# gnss_quectel_lc29hea.net
KiCad netlist of a schematic drawn in Altium Designer
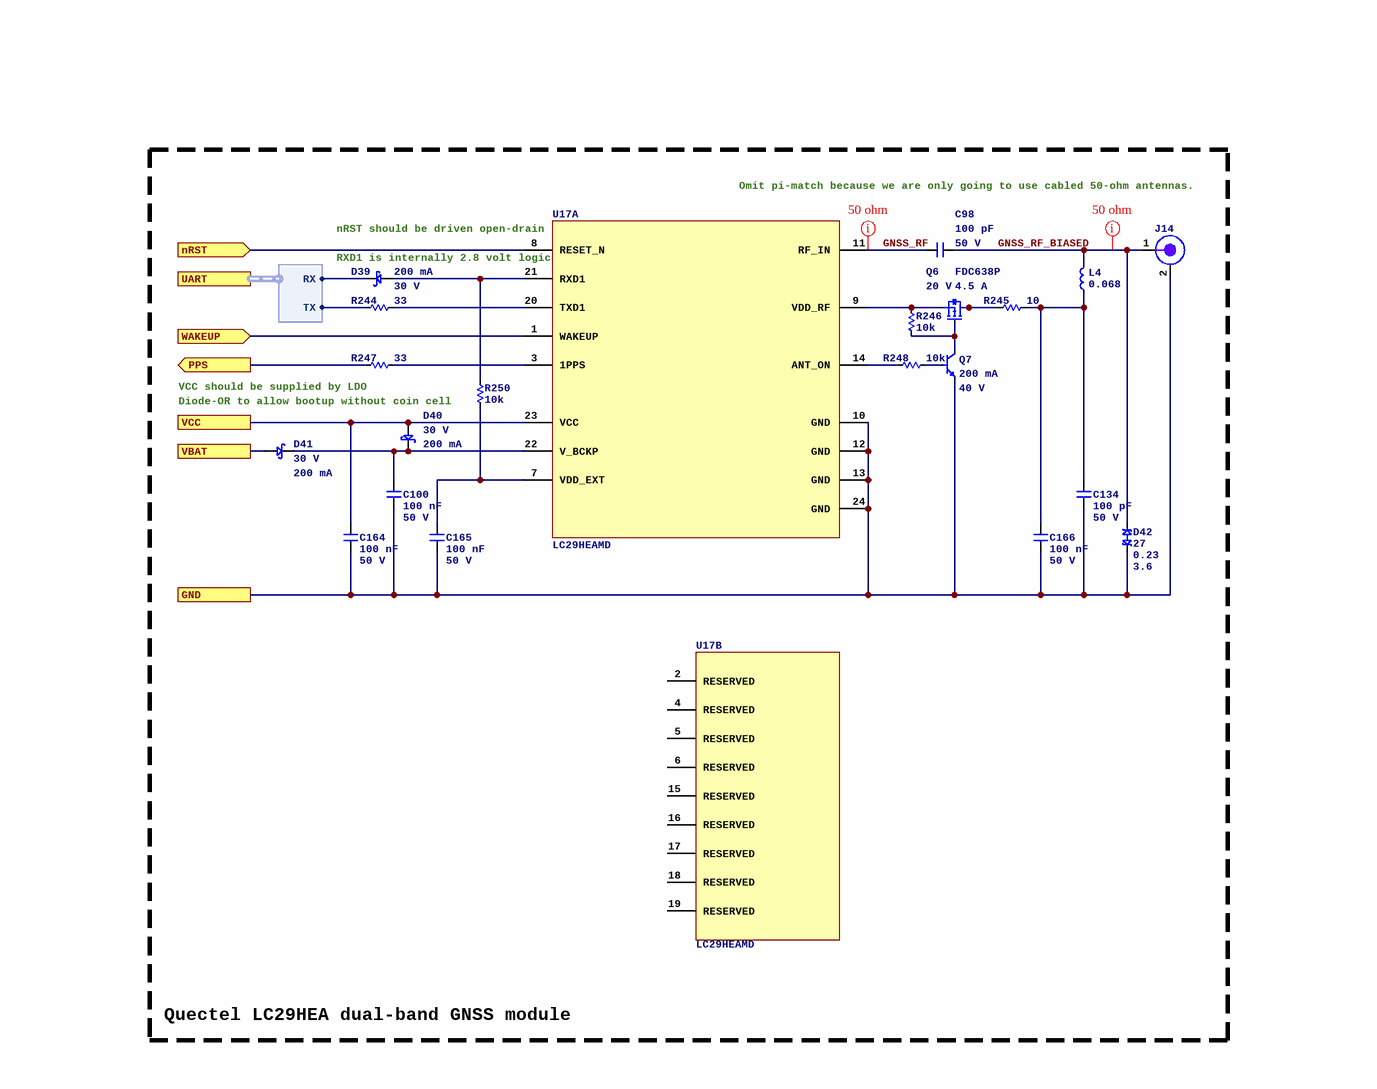
[diagram p0: gnss_quectel_lc29hea.SchDoc]

(export (version "E")
  (design (tool "Eeschema 10.0.6"))
  (components
    (comp (ref "C98")
      (value "0402CG101J500NT")
      (footprint "C0402")
      (fields
        (field (name "CAPACITANCE") "100 pF")
        (field (name "MANUFACTURER") "FH(Guangdong Fenghua Advanced Tech)")
        (field (name "VOLTAGE RATING") "50 V")
      )
      (libsource (lib "database") (part "__template_cap"))
    )
    (comp (ref "C100")
      (value "CL05B104KB54PNC")
      (footprint "C0402")
      (fields
        (field (name "CAPACITANCE") "100 nF")
        (field (name "MANUFACTURER") "Samsung Electro-Mechanics")
        (field (name "VOLTAGE RATING") "50 V")
      )
      (libsource (lib "database") (part "__template_cap"))
    )
    (comp (ref "C134")
      (value "0402CG101J500NT")
      (footprint "C0402")
      (fields
        (field (name "CAPACITANCE") "100 pF")
        (field (name "MANUFACTURER") "FH(Guangdong Fenghua Advanced Tech)")
        (field (name "VOLTAGE RATING") "50 V")
      )
      (libsource (lib "database") (part "__template_cap"))
    )
    (comp (ref "C164")
      (value "CL05B104KB54PNC")
      (footprint "C0402")
      (fields
        (field (name "CAPACITANCE") "100 nF")
        (field (name "MANUFACTURER") "Samsung Electro-Mechanics")
        (field (name "VOLTAGE RATING") "50 V")
      )
      (libsource (lib "database") (part "__template_cap"))
    )
    (comp (ref "C165")
      (value "CL05B104KB54PNC")
      (footprint "C0402")
      (fields
        (field (name "CAPACITANCE") "100 nF")
        (field (name "MANUFACTURER") "Samsung Electro-Mechanics")
        (field (name "VOLTAGE RATING") "50 V")
      )
      (libsource (lib "database") (part "__template_cap"))
    )
    (comp (ref "C166")
      (value "CL05B104KB54PNC")
      (footprint "C0402")
      (fields
        (field (name "CAPACITANCE") "100 nF")
        (field (name "MANUFACTURER") "Samsung Electro-Mechanics")
        (field (name "VOLTAGE RATING") "50 V")
      )
      (libsource (lib "database") (part "__template_cap"))
    )
    (comp (ref "D39")
      (value "BAT54XV2T1G")
      (footprint "SOD523")
      (description "ON Semi BAT54XV2T1G; SMT Schottky Diode; 30V 200mA; 5ns; 2-Pin SOD-523")
      (fields
        (field (name "MANUFACTURER") "onsemi")
        (field (name "CURRENT") "200 mA")
        (field (name "VR") "30 V")
      )
      (libsource (lib "database") (part "__template_diode_schottky"))
    )
    (comp (ref "D40")
      (value "BAT54XV2T1G")
      (footprint "SOD523")
      (description "ON Semi BAT54XV2T1G; SMT Schottky Diode; 30V 200mA; 5ns; 2-Pin SOD-523")
      (fields
        (field (name "MANUFACTURER") "onsemi")
        (field (name "CURRENT") "200 mA")
        (field (name "VR") "30 V")
      )
      (libsource (lib "database") (part "__template_diode_schottky"))
    )
    (comp (ref "D41")
      (value "BAT54XV2T1G")
      (footprint "SOD523")
      (description "ON Semi BAT54XV2T1G; SMT Schottky Diode; 30V 200mA; 5ns; 2-Pin SOD-523")
      (fields
        (field (name "MANUFACTURER") "onsemi")
        (field (name "CURRENT") "200 mA")
        (field (name "VR") "30 V")
      )
      (libsource (lib "database") (part "__template_diode_schottky"))
    )
    (comp (ref "D42")
      (value "TPD1E01B04DPYR")
      (footprint "TI_DPY0002A")
      (description "3.6 V bidirectional ESD protection diode for high-speed data lines")
      (fields
        (field (name "MANUFACTURER") "Texas Instruments")
        (field (name "POWER (W)") "27")
        (field (name "CAPACITANCE (PF)") "0.23")
        (field (name "STANDOFF (V)") "3.6")
      )
      (libsource (lib "database") (part "__template_diode_tvs_bi"))
    )
    (comp (ref "J14")
      (value "RFPC-SMA14-FN-A")
      (footprint "GCT_RFPC-SMA14-FN-A")
      (description "SMA Connector Jack, Female Socket Panel Mount, Through Hole, Right Angle Solder, IP68 unmated")
      (fields (field (name "MANUFACTURER") "GCT (Gradconn)"))
      (libsource (lib "database") (part "RFPC-SMA14-FN-A"))
    )
    (comp (ref "L4")
      (value "LQW18AN68NJ80D")
      (footprint "L0603_0.95MM")
      (description "68 nH chip inductor, ±5%")
      (fields (field (name "MANUFACTURER") "Murata") (field (name "INDUCTANCE (ΜH)") "0.068"))
      (libsource (lib "database") (part "__template_inductor"))
    )
    (comp (ref "Q6")
      (value "FDC638P")
      (footprint "6SOT23")
      (description "MOSFET P-CH 20V 4.5A SSOT-6")
      (fields
        (field (name "MANUFACTURER") "onsemi")
        (field (name "VOLTAGE") "20 V")
        (field (name "CURRENT") "4.5 A")
      )
      (libsource (lib "database") (part "FDC638P"))
    )
    (comp (ref "Q7")
      (value "MMBT3904T")
      (footprint "3SOT523")
      (description "Bipolar (BJT) Transistor NPN 40 V 200 mA 300MHz 150 mW Surface Mount SOT-523")
      (fields
        (field (name "MANUFACTURER") "Shenzhen Slkormicro Semicon Co., Ltd.")
        (field (name "CURRENT") "200 mA")
        (field (name "VOLTAGE") "40 V")
      )
      (libsource (lib "database") (part "MMBT3904T"))
    )
    (comp (ref "R244")
      (value "33")
      (footprint "R0402")
      (fields
        (field (name "TOLERANCE") "1%")
        (field (name "MANUFACTURER PART NUMBER") "0402WGF330JTCE")
        (field (name "MANUFACTURER") "UNI-ROYAL(Uniroyal Elec)")
      )
      (libsource (lib "database") (part "__template_resistor"))
    )
    (comp (ref "R245")
      (value "10")
      (footprint "R2512")
      (fields
        (field (name "TOLERANCE") "1%")
        (field (name "MANUFACTURER PART NUMBER") "RTT2510R0FTE")
        (field (name "MANUFACTURER") "RALEC")
      )
      (libsource (lib "database") (part "__template_resistor"))
    )
    (comp (ref "R246")
      (value "10k")
      (footprint "R0402")
      (fields
        (field (name "TOLERANCE") "1%")
        (field (name "MANUFACTURER PART NUMBER") "0402WGF1002TCE")
        (field (name "MANUFACTURER") "UNI-ROYAL(Uniroyal Elec)")
      )
      (libsource (lib "database") (part "__template_resistor"))
    )
    (comp (ref "R247")
      (value "33")
      (footprint "R0402")
      (fields
        (field (name "TOLERANCE") "1%")
        (field (name "MANUFACTURER PART NUMBER") "0402WGF330JTCE")
        (field (name "MANUFACTURER") "UNI-ROYAL(Uniroyal Elec)")
      )
      (libsource (lib "database") (part "__template_resistor"))
    )
    (comp (ref "R248")
      (value "10k")
      (footprint "R0402")
      (fields
        (field (name "TOLERANCE") "1%")
        (field (name "MANUFACTURER PART NUMBER") "0402WGF1002TCE")
        (field (name "MANUFACTURER") "UNI-ROYAL(Uniroyal Elec)")
      )
      (libsource (lib "database") (part "__template_resistor"))
    )
    (comp (ref "R250")
      (value "10k")
      (footprint "R0402")
      (fields
        (field (name "TOLERANCE") "1%")
        (field (name "MANUFACTURER PART NUMBER") "0402WGF1002TCE")
        (field (name "MANUFACTURER") "UNI-ROYAL(Uniroyal Elec)")
      )
      (libsource (lib "database") (part "__template_resistor"))
    )
    (comp (ref "U17")
      (value "LC29HEAMD")
      (footprint "QUECTEL_LC29H")
      (description "Rf Txrx Module Navigation SMD")
      (fields (field (name "MANUFACTURER") "Quectel"))
      (libsource (lib "database") (part "LC29HEAMD"))
    )
  )
  (nets
    (net (code "2") (name "/GND") (class "Default")
      (node (ref "C100") (pin "2") (pintype "passive"))
      (node (ref "C134") (pin "2") (pintype "passive"))
      (node (ref "C164") (pin "2") (pintype "passive"))
      (node (ref "C165") (pin "2") (pintype "passive"))
      (node (ref "C166") (pin "2") (pintype "passive"))
      (node (ref "D42") (pin "1") (pintype "passive"))
      (node (ref "J14") (pin "2") (pinfunction "GND_2") (pintype "passive"))
      (node (ref "Q7") (pin "2") (pinfunction "E_2") (pintype "passive"))
      (node (ref "U17") (pin "10") (pinfunction "GND_10") (pintype "passive"))
      (node (ref "U17") (pin "12") (pinfunction "GND_12") (pintype "passive"))
      (node (ref "U17") (pin "13") (pinfunction "GND_13") (pintype "passive"))
      (node (ref "U17") (pin "24") (pinfunction "GND_24") (pintype "passive"))
    )
    (net (code "3") (name "/GNSS_RF") (class "Default")
      (node (ref "C98") (pin "1") (pintype "passive"))
      (node (ref "U17") (pin "11") (pinfunction "RF_IN_11") (pintype "passive"))
    )
    (net (code "4") (name "/GNSS_RF_BIASED") (class "Default")
      (node (ref "C98") (pin "2") (pintype "passive"))
      (node (ref "D42") (pin "2") (pintype "passive"))
      (node (ref "J14") (pin "1") (pinfunction "RF_1") (pintype "passive"))
      (node (ref "L4") (pin "2") (pintype "passive"))
    )
    (net (code "5") (name "/PPS") (class "Default") (node (ref "R247") (pin "2") (pintype "passive")))
    (net (code "6") (name "/RX") (class "Default") (node (ref "D39") (pin "2") (pintype "passive")))
    (net (code "7") (name "/TX") (class "Default") (node (ref "R244") (pin "2") (pintype "passive")))
    (net (code "8") (name "/VBAT") (class "Default") (node (ref "D41") (pin "1") (pintype "passive")))
    (net (code "9") (name "/VCC") (class "Default")
      (node (ref "C164") (pin "1") (pintype "passive"))
      (node (ref "D40") (pin "1") (pintype "passive"))
      (node (ref "U17") (pin "23") (pinfunction "VCC_23") (pintype "passive"))
    )
    (net (code "10") (name "/WAKEUP") (class "Default")
      (node (ref "U17") (pin "1") (pinfunction "WAKEUP_1") (pintype "passive"))
    )
    (net (code "11") (name "/nRST") (class "Default")
      (node (ref "U17") (pin "8") (pinfunction "RESET_N_8") (pintype "passive"))
    )
    (net (code "13") (name "Net-(C134-Pad1)") (class "Default")
      (node (ref "C134") (pin "1") (pintype "passive"))
      (node (ref "C166") (pin "1") (pintype "passive"))
      (node (ref "L4") (pin "1") (pintype "passive"))
      (node (ref "R245") (pin "1") (pintype "passive"))
    )
    (net (code "14") (name "Net-(Q6-Pad1)") (class "Default")
      (node (ref "Q6") (pin "1") (pintype "passive"))
      (node (ref "Q6") (pin "2") (pintype "passive"))
      (node (ref "Q6") (pin "5") (pintype "passive"))
      (node (ref "Q6") (pin "6") (pintype "passive"))
      (node (ref "R245") (pin "2") (pintype "passive"))
    )
    (net (code "15") (name "Net-(Q7-B)") (class "Default")
      (node (ref "Q7") (pin "1") (pinfunction "B_1") (pintype "passive"))
      (node (ref "R248") (pin "1") (pintype "passive"))
    )
    (net (code "16") (name "Net-(Q7-C)") (class "Default")
      (node (ref "Q6") (pin "3") (pintype "passive"))
      (node (ref "Q7") (pin "3") (pinfunction "C_3") (pintype "passive"))
      (node (ref "R246") (pin "2") (pintype "passive"))
    )
    (net (code "17") (name "Net-(U17A-1PPS)") (class "Default")
      (node (ref "R247") (pin "1") (pintype "passive"))
      (node (ref "U17") (pin "3") (pinfunction "1PPS_3") (pintype "passive"))
    )
    (net (code "18") (name "Net-(U17A-ANT_ON)") (class "Default")
      (node (ref "R248") (pin "2") (pintype "passive"))
      (node (ref "U17") (pin "14") (pinfunction "ANT_ON_14") (pintype "passive"))
    )
    (net (code "19") (name "Net-(U17A-RXD1)") (class "Default")
      (node (ref "D39") (pin "1") (pintype "passive"))
      (node (ref "R250") (pin "1") (pintype "passive"))
      (node (ref "U17") (pin "21") (pinfunction "RXD1_21") (pintype "passive"))
    )
    (net (code "20") (name "Net-(U17A-TXD1)") (class "Default")
      (node (ref "R244") (pin "1") (pintype "passive"))
      (node (ref "U17") (pin "20") (pinfunction "TXD1_20") (pintype "passive"))
    )
    (net (code "21") (name "Net-(U17A-VDD_EXT)") (class "Default")
      (node (ref "C165") (pin "1") (pintype "passive"))
      (node (ref "R250") (pin "2") (pintype "passive"))
      (node (ref "U17") (pin "7") (pinfunction "VDD_EXT_7") (pintype "passive"))
    )
    (net (code "22") (name "Net-(U17A-VDD_RF)") (class "Default")
      (node (ref "Q6") (pin "4") (pintype "passive"))
      (node (ref "R246") (pin "1") (pintype "passive"))
      (node (ref "U17") (pin "9") (pinfunction "VDD_RF_9") (pintype "passive"))
    )
    (net (code "23") (name "Net-(U17A-V_BCKP)") (class "Default")
      (node (ref "C100") (pin "1") (pintype "passive"))
      (node (ref "D40") (pin "2") (pintype "passive"))
      (node (ref "D41") (pin "2") (pintype "passive"))
      (node (ref "U17") (pin "22") (pinfunction "V_BCKP_22") (pintype "passive"))
    )
    (net (code "24") (name "unconnected-(U17B-RESERVED-Pad2)") (class "Default")
      (node (ref "U17") (pin "2") (pinfunction "RESERVED_2") (pintype "passive"))
    )
    (net (code "25") (name "unconnected-(U17B-RESERVED-Pad4)") (class "Default")
      (node (ref "U17") (pin "4") (pinfunction "RESERVED_4") (pintype "passive"))
    )
    (net (code "26") (name "unconnected-(U17B-RESERVED-Pad5)") (class "Default")
      (node (ref "U17") (pin "5") (pinfunction "RESERVED_5") (pintype "passive"))
    )
    (net (code "27") (name "unconnected-(U17B-RESERVED-Pad6)") (class "Default")
      (node (ref "U17") (pin "6") (pinfunction "RESERVED_6") (pintype "passive"))
    )
    (net (code "28") (name "unconnected-(U17B-RESERVED-Pad15)") (class "Default")
      (node (ref "U17") (pin "15") (pinfunction "RESERVED_15") (pintype "passive"))
    )
    (net (code "29") (name "unconnected-(U17B-RESERVED-Pad16)") (class "Default")
      (node (ref "U17") (pin "16") (pinfunction "RESERVED_16") (pintype "passive"))
    )
    (net (code "30") (name "unconnected-(U17B-RESERVED-Pad17)") (class "Default")
      (node (ref "U17") (pin "17") (pinfunction "RESERVED_17") (pintype "passive"))
    )
    (net (code "31") (name "unconnected-(U17B-RESERVED-Pad18)") (class "Default")
      (node (ref "U17") (pin "18") (pinfunction "RESERVED_18") (pintype "passive"))
    )
    (net (code "32") (name "unconnected-(U17B-RESERVED-Pad19)") (class "Default")
      (node (ref "U17") (pin "19") (pinfunction "RESERVED_19") (pintype "passive"))
    )
  )
)
